# lightmeter_proto2.net
KiCad netlist of a schematic drawn in EAGLE
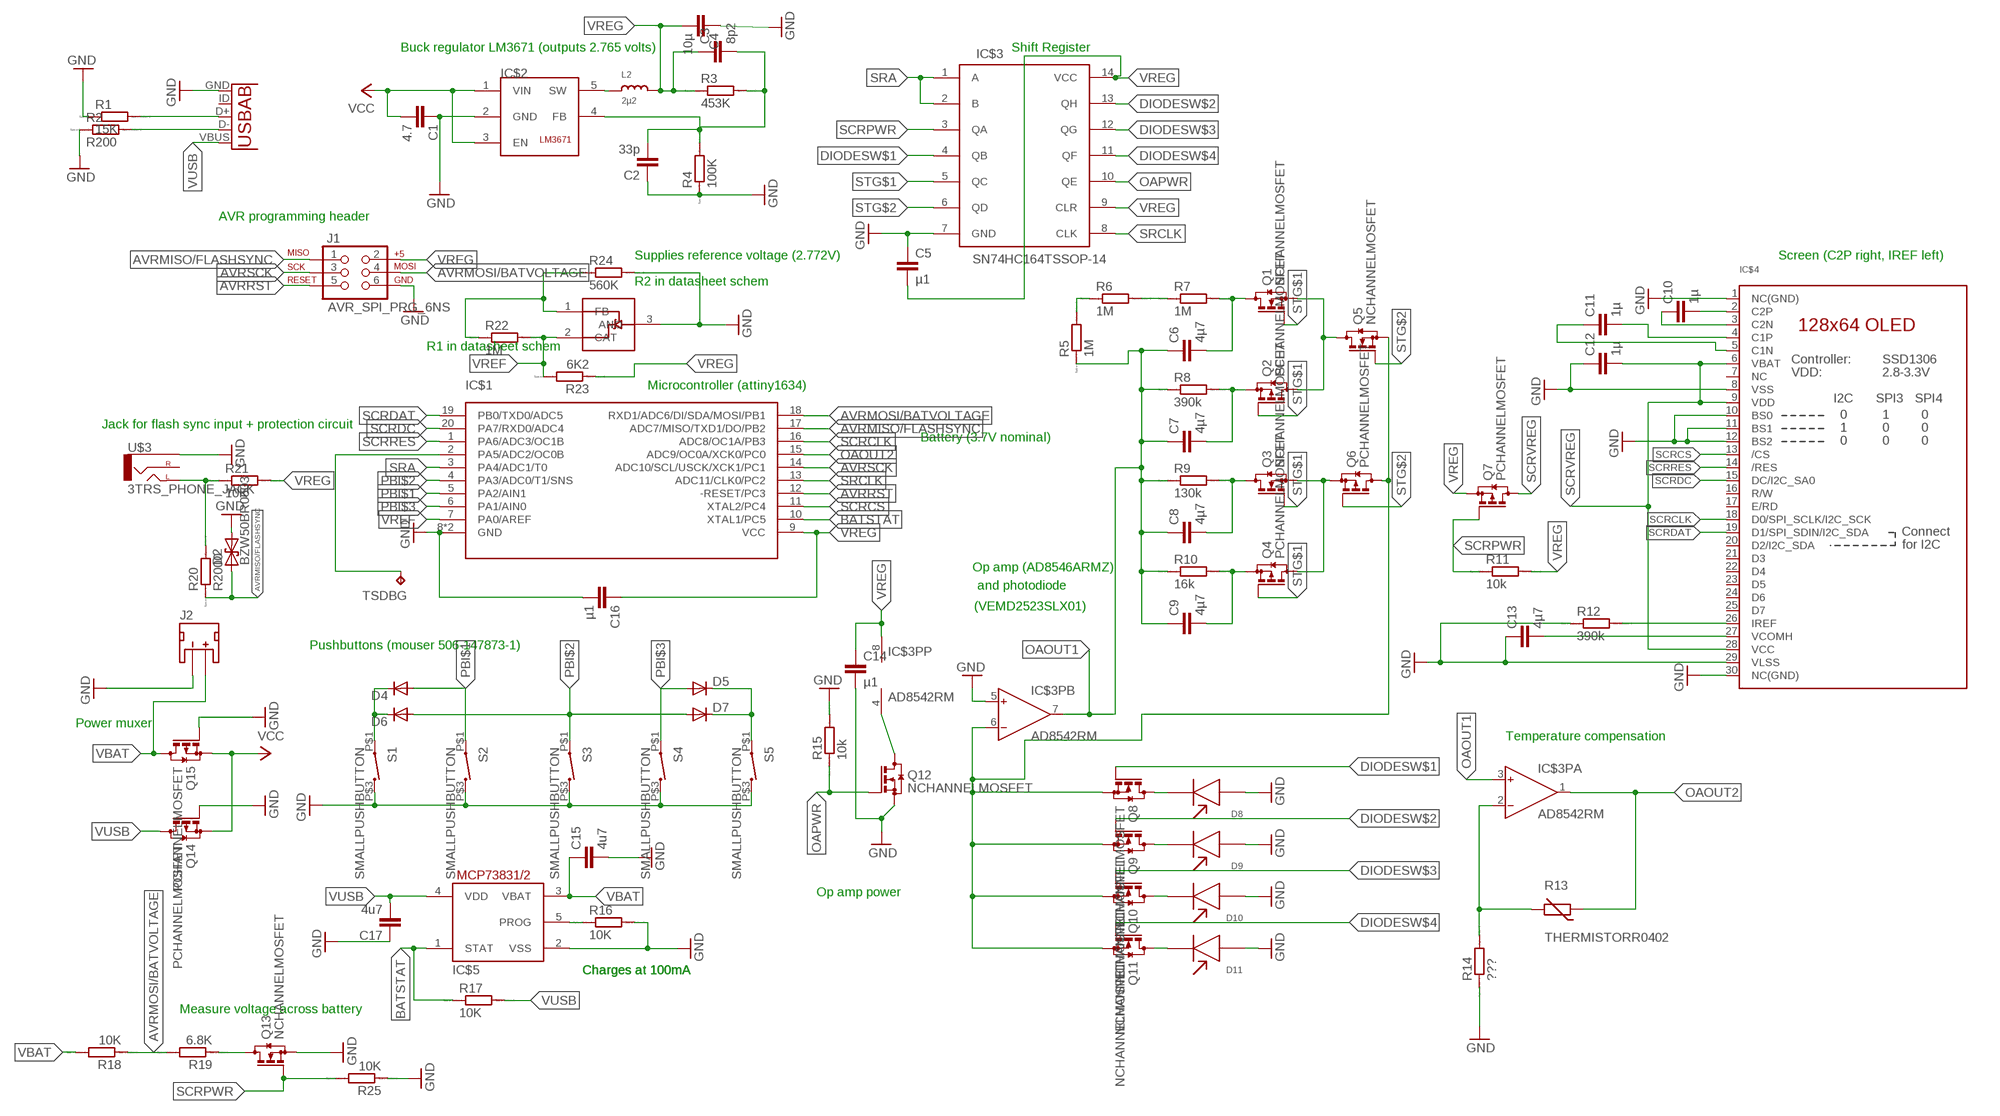
[diagram p0: schematic, sheet 1]

(export (version "E")
  (design (tool "Eeschema 10.0.6"))
  (components
    (comp (ref "C1")
      (value "4.7")
      (footprint "eagle-import:C0402")
      (libsource (lib "eagle-import") (part "C-EUC0402"))
    )
    (comp (ref "C2")
      (value "33p")
      (footprint "eagle-import:C0402")
      (libsource (lib "eagle-import") (part "C-EUC0402"))
    )
    (comp (ref "C3")
      (value "8p2")
      (footprint "eagle-import:C0402")
      (libsource (lib "eagle-import") (part "C-EUC0402"))
    )
    (comp (ref "C4")
      (value "10µ")
      (footprint "eagle-import:C0402")
      (libsource (lib "eagle-import") (part "C-EUC0402"))
    )
    (comp (ref "C5")
      (value "µ1")
      (footprint "eagle-import:C0402")
      (libsource (lib "eagle-import") (part "C-EUC0402"))
    )
    (comp (ref "C6")
      (value "4µ7")
      (footprint "eagle-import:C0402")
      (libsource (lib "eagle-import") (part "C-EUC0402"))
    )
    (comp (ref "C7")
      (value "4µ7")
      (footprint "eagle-import:C0402")
      (libsource (lib "eagle-import") (part "C-EUC0402"))
    )
    (comp (ref "C8")
      (value "4µ7")
      (footprint "eagle-import:C0402")
      (libsource (lib "eagle-import") (part "C-EUC0402"))
    )
    (comp (ref "C9")
      (value "4µ7")
      (footprint "eagle-import:C0402")
      (libsource (lib "eagle-import") (part "C-EUC0402"))
    )
    (comp (ref "C10")
      (value "1µ")
      (footprint "eagle-import:C0402")
      (libsource (lib "eagle-import") (part "C-EUC0402"))
    )
    (comp (ref "C11")
      (value "1µ")
      (footprint "eagle-import:C0402")
      (libsource (lib "eagle-import") (part "C-EUC0402"))
    )
    (comp (ref "C12")
      (value "1µ")
      (footprint "eagle-import:C0402")
      (libsource (lib "eagle-import") (part "C-EUC0402"))
    )
    (comp (ref "C13")
      (value "4µ7")
      (footprint "eagle-import:C0402")
      (libsource (lib "eagle-import") (part "C-EUC0402"))
    )
    (comp (ref "C14")
      (value "µ1")
      (footprint "eagle-import:C0402")
      (libsource (lib "eagle-import") (part "C-EUC0402"))
    )
    (comp (ref "C15")
      (value "4u7")
      (footprint "eagle-import:C0402")
      (libsource (lib "eagle-import") (part "C-EUC0402"))
    )
    (comp (ref "C16")
      (value "µ1")
      (footprint "eagle-import:C0402")
      (libsource (lib "eagle-import") (part "C-EUC0402"))
    )
    (comp (ref "C17")
      (value "4u7")
      (footprint "eagle-import:C0402")
      (libsource (lib "eagle-import") (part "C-EUC0402"))
    )
    (comp (ref "D2")
      (value "BZW50BR0603")
      (footprint "eagle-import:R0603")
      (libsource (lib "eagle-import") (part "BZW50BR0603"))
    )
    (comp (ref "D4")
      (value "DIODE-SOD323-W")
      (footprint "eagle-import:SOD323-W")
      (libsource (lib "eagle-import") (part "DIODE-SOD323-W"))
    )
    (comp (ref "D5")
      (value "DIODE-SOD323-W")
      (footprint "eagle-import:SOD323-W")
      (libsource (lib "eagle-import") (part "DIODE-SOD323-W"))
    )
    (comp (ref "D6")
      (value "DIODE-SOD323-W")
      (footprint "eagle-import:SOD323-W")
      (libsource (lib "eagle-import") (part "DIODE-SOD323-W"))
    )
    (comp (ref "D7")
      (value "DIODE-SOD323-W")
      (footprint "eagle-import:SOD323-W")
      (libsource (lib "eagle-import") (part "DIODE-SOD323-W"))
    )
    (comp (ref "D8")
      (value "VEMD2523SLX01")
      (footprint "eagle-import:VEMD2523SLX01")
      (libsource (lib "eagle-import") (part "VEMD2523SLX01"))
    )
    (comp (ref "D9")
      (value "VEMD2523SLX01")
      (footprint "eagle-import:VEMD2523SLX01")
      (libsource (lib "eagle-import") (part "VEMD2523SLX01"))
    )
    (comp (ref "D10")
      (value "VEMD2523SLX01")
      (footprint "eagle-import:VEMD2523SLX01")
      (libsource (lib "eagle-import") (part "VEMD2523SLX01"))
    )
    (comp (ref "D11")
      (value "VEMD2523SLX01")
      (footprint "eagle-import:VEMD2523SLX01")
      (libsource (lib "eagle-import") (part "VEMD2523SLX01"))
    )
    (comp (ref "IC$1")
      (value "ATTINY1634MLF20")
      (footprint "eagle-import:MLF20")
      (libsource (lib "eagle-import") (part "ATTINY1634MLF20"))
    )
    (comp (ref "IC$2")
      (value "LM3671")
      (footprint "eagle-import:SOT23-5")
      (libsource (lib "eagle-import") (part "LM3671"))
    )
    (comp (ref "IC$3")
      (value "SN74HC164TSSOP-14")
      (footprint "eagle-import:TSSOP14")
      (libsource (lib "eagle-import") (part "SN74HC164TSSOP-14"))
    )
    (comp (ref "IC$3P")
      (value "AD8542RM")
      (footprint "eagle-import:MSOP08")
      (fields (field (name "MPN") "AD8542ARZ"))
      (libsource (lib "eagle-import") (part "AD8542RM"))
    )
    (comp (ref "IC$4")
      (value "DISP_OLED_UG-2864HSWEG010.96\"")
      (footprint "eagle-import:UG-2864HSWEG01_0.96IN_WRAPAROUND")
      (libsource (lib "eagle-import") (part "DISP_OLED_UG-2864HSWEG010.96{dblquote}"))
    )
    (comp (ref "IC$5")
      (value "MCP73831/OT")
      (footprint "eagle-import:SOT23-5L")
      (libsource (lib "eagle-import") (part "MCP73831/OT"))
    )
    (comp (ref "IC$6")
      (value "TL4051")
      (footprint "eagle-import:SOT23")
      (libsource (lib "eagle-import") (part "TL4051"))
    )
    (comp (ref "J1")
      (value "AVR_SPI_PRG_6NS")
      (footprint "eagle-import:2X3-NS")
      (libsource (lib "eagle-import") (part "AVR_SPI_PRG_6NS"))
    )
    (comp (ref "J2")
      (value "JST_2MM_MALE")
      (footprint "eagle-import:JST-2-SMD")
      (libsource (lib "eagle-import") (part "JST_2MM_MALE"))
    )
    (comp (ref "L2")
      (value "2µ2")
      (footprint "eagle-import:_0402")
      (libsource (lib "eagle-import") (part "INDUCTOR_0402"))
    )
    (comp (ref "Q1")
      (value "NCHANNELMOSFET")
      (footprint "eagle-import:SOT-416-3")
      (libsource (lib "eagle-import") (part "NCHANNELMOSFET"))
    )
    (comp (ref "Q2")
      (value "PCHANNELMOSFET")
      (footprint "eagle-import:SOT-416-3")
      (libsource (lib "eagle-import") (part "PCHANNELMOSFET"))
    )
    (comp (ref "Q3")
      (value "NCHANNELMOSFET")
      (footprint "eagle-import:SOT-416-3")
      (libsource (lib "eagle-import") (part "NCHANNELMOSFET"))
    )
    (comp (ref "Q4")
      (value "PCHANNELMOSFET")
      (footprint "eagle-import:SOT-416-3")
      (libsource (lib "eagle-import") (part "PCHANNELMOSFET"))
    )
    (comp (ref "Q5")
      (value "NCHANNELMOSFET")
      (footprint "eagle-import:SOT-416-3")
      (libsource (lib "eagle-import") (part "NCHANNELMOSFET"))
    )
    (comp (ref "Q6")
      (value "PCHANNELMOSFET")
      (footprint "eagle-import:SOT-416-3")
      (libsource (lib "eagle-import") (part "PCHANNELMOSFET"))
    )
    (comp (ref "Q7")
      (value "PCHANNELMOSFET")
      (footprint "eagle-import:SOT-416-3")
      (libsource (lib "eagle-import") (part "PCHANNELMOSFET"))
    )
    (comp (ref "Q8")
      (value "NCHANNELMOSFET")
      (footprint "eagle-import:SOT-416-3")
      (libsource (lib "eagle-import") (part "NCHANNELMOSFET"))
    )
    (comp (ref "Q9")
      (value "NCHANNELMOSFET")
      (footprint "eagle-import:SOT-416-3")
      (libsource (lib "eagle-import") (part "NCHANNELMOSFET"))
    )
    (comp (ref "Q10")
      (value "NCHANNELMOSFET")
      (footprint "eagle-import:SOT-416-3")
      (libsource (lib "eagle-import") (part "NCHANNELMOSFET"))
    )
    (comp (ref "Q11")
      (value "NCHANNELMOSFET")
      (footprint "eagle-import:SOT-416-3")
      (libsource (lib "eagle-import") (part "NCHANNELMOSFET"))
    )
    (comp (ref "Q12")
      (value "NCHANNELMOSFET")
      (footprint "eagle-import:SOT-416-3")
      (libsource (lib "eagle-import") (part "NCHANNELMOSFET"))
    )
    (comp (ref "Q13")
      (value "NCHANNELMOSFET")
      (footprint "eagle-import:SOT-416-3")
      (libsource (lib "eagle-import") (part "NCHANNELMOSFET"))
    )
    (comp (ref "Q14")
      (value "PCHANNELMOSFET")
      (footprint "eagle-import:SOT-416-3")
      (libsource (lib "eagle-import") (part "PCHANNELMOSFET"))
    )
    (comp (ref "Q15")
      (value "PCHANNELMOSFET")
      (footprint "eagle-import:SOT-416-3")
      (libsource (lib "eagle-import") (part "PCHANNELMOSFET"))
    )
    (comp (ref "R1")
      (value "15K")
      (footprint "eagle-import:R0402")
      (libsource (lib "eagle-import") (part "R-EU_R0402"))
    )
    (comp (ref "R2")
      (value "R200")
      (footprint "eagle-import:R0402")
      (libsource (lib "eagle-import") (part "R-EU_R0402"))
    )
    (comp (ref "R3")
      (value "453K")
      (footprint "eagle-import:R0402")
      (libsource (lib "eagle-import") (part "R-EU_R0402"))
    )
    (comp (ref "R4")
      (value "100K")
      (footprint "eagle-import:R0402")
      (libsource (lib "eagle-import") (part "R-EU_R0402"))
    )
    (comp (ref "R5")
      (value "1M")
      (footprint "eagle-import:R0402")
      (libsource (lib "eagle-import") (part "R-EU_R0402"))
    )
    (comp (ref "R6")
      (value "1M")
      (footprint "eagle-import:R0402")
      (libsource (lib "eagle-import") (part "R-EU_R0402"))
    )
    (comp (ref "R7")
      (value "1M")
      (footprint "eagle-import:R0402")
      (libsource (lib "eagle-import") (part "R-EU_R0402"))
    )
    (comp (ref "R8")
      (value "390k")
      (footprint "eagle-import:R0402")
      (libsource (lib "eagle-import") (part "R-EU_R0402"))
    )
    (comp (ref "R9")
      (value "130k")
      (footprint "eagle-import:R0402")
      (libsource (lib "eagle-import") (part "R-EU_R0402"))
    )
    (comp (ref "R10")
      (value "16k")
      (footprint "eagle-import:R0402")
      (libsource (lib "eagle-import") (part "R-EU_R0402"))
    )
    (comp (ref "R11")
      (value "10k")
      (footprint "eagle-import:R0402")
      (libsource (lib "eagle-import") (part "R-EU_R0402"))
    )
    (comp (ref "R12")
      (value "390k")
      (footprint "eagle-import:R0402")
      (libsource (lib "eagle-import") (part "R-EU_R0402"))
    )
    (comp (ref "R13")
      (value "THERMISTORR0402")
      (footprint "eagle-import:R0402")
      (libsource (lib "eagle-import") (part "THERMISTORR0402"))
    )
    (comp (ref "R14")
      (value "???")
      (footprint "eagle-import:R0402")
      (libsource (lib "eagle-import") (part "R-EU_R0402"))
    )
    (comp (ref "R15")
      (value "10k")
      (footprint "eagle-import:R0402")
      (libsource (lib "eagle-import") (part "R-EU_R0402"))
    )
    (comp (ref "R16")
      (value "10K")
      (footprint "eagle-import:R0402")
      (libsource (lib "eagle-import") (part "R-EU_R0402"))
    )
    (comp (ref "R17")
      (value "10K")
      (footprint "eagle-import:R0402")
      (libsource (lib "eagle-import") (part "R-EU_R0402"))
    )
    (comp (ref "R18")
      (value "10K")
      (footprint "eagle-import:R0402")
      (libsource (lib "eagle-import") (part "R-EU_R0402"))
    )
    (comp (ref "R19")
      (value "6.8K")
      (footprint "eagle-import:R0402")
      (libsource (lib "eagle-import") (part "R-EU_R0402"))
    )
    (comp (ref "R20")
      (value "R2000")
      (footprint "eagle-import:R0402")
      (libsource (lib "eagle-import") (part "R-EU_R0402"))
    )
    (comp (ref "R21")
      (value "10K")
      (footprint "eagle-import:R0402")
      (libsource (lib "eagle-import") (part "R-EU_R0402"))
    )
    (comp (ref "R22")
      (value "1M")
      (footprint "eagle-import:R0402")
      (libsource (lib "eagle-import") (part "R-EU_R0402"))
    )
    (comp (ref "R23")
      (value "6K2")
      (footprint "eagle-import:R0402")
      (libsource (lib "eagle-import") (part "R-EU_R0402"))
    )
    (comp (ref "R24")
      (value "560K")
      (footprint "eagle-import:R0402")
      (libsource (lib "eagle-import") (part "R-EU_R0402"))
    )
    (comp (ref "R25")
      (value "10K")
      (footprint "eagle-import:R0402")
      (libsource (lib "eagle-import") (part "R-EU_R0402"))
    )
    (comp (ref "S1")
      (value "SMALLPUSHBUTTON")
      (footprint "eagle-import:BUTTON")
      (libsource (lib "eagle-import") (part "SMALLPUSHBUTTON"))
    )
    (comp (ref "S2")
      (value "SMALLPUSHBUTTON")
      (footprint "eagle-import:BUTTON")
      (libsource (lib "eagle-import") (part "SMALLPUSHBUTTON"))
    )
    (comp (ref "S3")
      (value "SMALLPUSHBUTTON")
      (footprint "eagle-import:BUTTON")
      (libsource (lib "eagle-import") (part "SMALLPUSHBUTTON"))
    )
    (comp (ref "S4")
      (value "SMALLPUSHBUTTON")
      (footprint "eagle-import:BUTTON")
      (libsource (lib "eagle-import") (part "SMALLPUSHBUTTON"))
    )
    (comp (ref "S5")
      (value "SMALLPUSHBUTTON")
      (footprint "eagle-import:BUTTON")
      (libsource (lib "eagle-import") (part "SMALLPUSHBUTTON"))
    )
    (comp (ref "TSDBG")
      (value "TPPAD1-13")
      (footprint "eagle-import:P1-13")
      (libsource (lib "eagle-import") (part "TPPAD1-13"))
    )
    (comp (ref "U$3")
      (value "3TRS_PHONE_JACK")
      (footprint "eagle-import:3TRS-SMD")
      (libsource (lib "eagle-import") (part "3TRS_PHONE_JACK"))
    )
    (comp (ref "U2")
      (value "USB-AB\"")
      (footprint "eagle-import:USB_AB_MICRO_1_1_V2")
      (libsource (lib "eagle-import") (part "USB-AB{dblquote}"))
    )
  )
  (nets
    (net (code "1") (name "AVRMISO{slash}FLASHSYNC") (class "Default")
      (node (ref "D2") (pin "1") (pinfunction "1_1") (pintype "passive"))
      (node (ref "IC$1") (pin "17") (pinfunction "ADC7/MISO/TXD1/DO/PB2_17") (pintype "bidirectional"))
      (node (ref "J1") (pin "1") (pinfunction "1_1") (pintype "passive"))
      (node (ref "R20") (pin "1") (pinfunction "1_1") (pintype "passive"))
    )
    (net (code "2") (name "AVRMOSI{slash}BATVOLTAGE") (class "Default")
      (node (ref "IC$1") (pin "18") (pinfunction "RXD1/ADC6/DI/SDA/MOSI/PB1_18") (pintype "bidirectional"))
      (node (ref "J1") (pin "4") (pinfunction "4_4") (pintype "passive"))
      (node (ref "R18") (pin "1") (pinfunction "1_1") (pintype "passive"))
      (node (ref "R19") (pin "2") (pinfunction "2_2") (pintype "passive"))
    )
    (net (code "3") (name "AVRRST") (class "Default")
      (node (ref "IC$1") (pin "12") (pinfunction "-RESET/PC3_12") (pintype "bidirectional"))
      (node (ref "J1") (pin "5") (pinfunction "5_5") (pintype "passive"))
    )
    (net (code "4") (name "AVRSCK") (class "Default")
      (node (ref "IC$1") (pin "14") (pinfunction "ADC10/SCL/USCK/XCK1/PC1_14") (pintype "bidirectional"))
      (node (ref "J1") (pin "3") (pinfunction "3_3") (pintype "passive"))
    )
    (net (code "5") (name "BATSTAT") (class "Default")
      (node (ref "IC$1") (pin "10") (pinfunction "XTAL1/PC5_10") (pintype "bidirectional"))
      (node (ref "IC$5") (pin "1") (pinfunction "STAT_1") (pintype "output"))
      (node (ref "R17") (pin "1") (pinfunction "1_1") (pintype "passive"))
    )
    (net (code "6") (name "DIODESW$1") (class "Default")
      (node (ref "IC$3") (pin "4") (pinfunction "QB_4") (pintype "bidirectional"))
      (node (ref "Q8") (pin "P$1") (pinfunction "G_P$1") (pintype "passive"))
    )
    (net (code "7") (name "DIODESW$2") (class "Default")
      (node (ref "IC$3") (pin "13") (pinfunction "QH_13") (pintype "bidirectional"))
      (node (ref "Q9") (pin "P$1") (pinfunction "G_P$1") (pintype "passive"))
    )
    (net (code "8") (name "DIODESW$3") (class "Default")
      (node (ref "IC$3") (pin "12") (pinfunction "QG_12") (pintype "bidirectional"))
      (node (ref "Q10") (pin "P$1") (pinfunction "G_P$1") (pintype "passive"))
    )
    (net (code "9") (name "DIODESW$4") (class "Default")
      (node (ref "IC$3") (pin "11") (pinfunction "QF_11") (pintype "bidirectional"))
      (node (ref "Q11") (pin "P$1") (pinfunction "G_P$1") (pintype "passive"))
    )
    (net (code "10") (name "GND") (class "Default")
      (node (ref "C1") (pin "1") (pinfunction "1_1") (pintype "passive"))
      (node (ref "C12") (pin "1") (pinfunction "1_1") (pintype "passive"))
      (node (ref "C13") (pin "1") (pinfunction "1_1") (pintype "passive"))
      (node (ref "C14") (pin "2") (pinfunction "2_2") (pintype "passive"))
      (node (ref "C15") (pin "2") (pinfunction "2_2") (pintype "passive"))
      (node (ref "C16") (pin "2") (pinfunction "2_2") (pintype "passive"))
      (node (ref "C17") (pin "1") (pinfunction "1_1") (pintype "passive"))
      (node (ref "C2") (pin "1") (pinfunction "1_1") (pintype "passive"))
      (node (ref "C4") (pin "1") (pinfunction "1_1") (pintype "passive"))
      (node (ref "C5") (pin "1") (pinfunction "1_1") (pintype "passive"))
      (node (ref "D10") (pin "P$1") (pinfunction "P$1_P$1") (pintype "bidirectional"))
      (node (ref "D11") (pin "P$1") (pinfunction "P$1_P$1") (pintype "bidirectional"))
      (node (ref "D2") (pin "2") (pinfunction "2_2") (pintype "passive"))
      (node (ref "D8") (pin "P$1") (pinfunction "P$1_P$1") (pintype "bidirectional"))
      (node (ref "D9") (pin "P$1") (pinfunction "P$1_P$1") (pintype "bidirectional"))
      (node (ref "IC$1") (pin "8") (pinfunction "GND_8") (pintype "power_in"))
      (node (ref "IC$1") (pin "GND") (pinfunction "GND_GND") (pintype "power_in"))
      (node (ref "IC$2") (pin "2") (pinfunction "GND_2") (pintype "bidirectional"))
      (node (ref "IC$3") (pin "7") (pinfunction "GND_7") (pintype "bidirectional"))
      (node (ref "IC$3P") (pin "5") (pinfunction "IN+_5") (pintype "input"))
      (node (ref "IC$4") (pin "1") (pinfunction "NC(GND)_1") (pintype "input"))
      (node (ref "IC$4") (pin "10") (pinfunction "BS0_10") (pintype "input"))
      (node (ref "IC$4") (pin "11") (pinfunction "BS1_11") (pintype "input"))
      (node (ref "IC$4") (pin "12") (pinfunction "BS2_12") (pintype "input"))
      (node (ref "IC$4") (pin "29") (pinfunction "VLSS_29") (pintype "power_in"))
      (node (ref "IC$4") (pin "30") (pinfunction "NC(GND)_30") (pintype "input"))
      (node (ref "IC$4") (pin "8") (pinfunction "VSS_8") (pintype "power_in"))
      (node (ref "IC$5") (pin "2") (pinfunction "VSS_2") (pintype "power_in"))
      (node (ref "IC$6") (pin "3") (pinfunction "ANO_3") (pintype "bidirectional"))
      (node (ref "J1") (pin "6") (pinfunction "6_6") (pintype "passive"))
      (node (ref "J2") (pin "1") (pinfunction "-_1") (pintype "bidirectional"))
      (node (ref "Q12") (pin "P$2") (pinfunction "S_P$2") (pintype "passive"))
      (node (ref "Q13") (pin "P$2") (pinfunction "S_P$2") (pintype "passive"))
      (node (ref "Q14") (pin "P$1") (pinfunction "G_P$1") (pintype "passive"))
      (node (ref "Q15") (pin "P$1") (pinfunction "G_P$1") (pintype "passive"))
      (node (ref "R1") (pin "1") (pinfunction "1_1") (pintype "passive"))
      (node (ref "R12") (pin "1") (pinfunction "1_1") (pintype "passive"))
      (node (ref "R14") (pin "1") (pinfunction "1_1") (pintype "passive"))
      (node (ref "R15") (pin "2") (pinfunction "2_2") (pintype "passive"))
      (node (ref "R16") (pin "2") (pinfunction "2_2") (pintype "passive"))
      (node (ref "R2") (pin "1") (pinfunction "1_1") (pintype "passive"))
      (node (ref "R24") (pin "2") (pinfunction "2_2") (pintype "passive"))
      (node (ref "R25") (pin "1") (pinfunction "1_1") (pintype "passive"))
      (node (ref "R4") (pin "1") (pinfunction "1_1") (pintype "passive"))
      (node (ref "S1") (pin "P$3") (pinfunction "2_P$3") (pintype "passive"))
      (node (ref "S2") (pin "P$3") (pinfunction "2_P$3") (pintype "passive"))
      (node (ref "S3") (pin "P$3") (pinfunction "2_P$3") (pintype "passive"))
      (node (ref "S4") (pin "P$3") (pinfunction "2_P$3") (pintype "passive"))
      (node (ref "S5") (pin "P$3") (pinfunction "2_P$3") (pintype "passive"))
      (node (ref "U$3") (pin "P$1") (pinfunction "SLEEVE_P$1") (pintype "bidirectional"))
      (node (ref "U2") (pin "GND") (pinfunction "GND_GND") (pintype "bidirectional"))
    )
    (net (code "11") (name "Net-(IC$1-PA5{slash}ADC2{slash}OC0B)") (class "Default")
      (node (ref "IC$1") (pin "2") (pinfunction "PA5/ADC2/OC0B_2") (pintype "bidirectional"))
      (node (ref "TSDBG") (pin "TP") (pinfunction "TP_TP") (pintype "input"))
    )
    (net (code "12") (name "Net-(IC$2-FB)") (class "Default")
      (node (ref "C2") (pin "2") (pinfunction "2_2") (pintype "passive"))
      (node (ref "C3") (pin "2") (pinfunction "2_2") (pintype "passive"))
      (node (ref "IC$2") (pin "4") (pinfunction "FB_4") (pintype "bidirectional"))
      (node (ref "R3") (pin "2") (pinfunction "2_2") (pintype "passive"))
      (node (ref "R4") (pin "2") (pinfunction "2_2") (pintype "passive"))
    )
    (net (code "13") (name "Net-(IC$2-SW)") (class "Default")
      (node (ref "IC$2") (pin "5") (pinfunction "SW_5") (pintype "bidirectional"))
      (node (ref "L2") (pin "1") (pinfunction "1_1") (pintype "passive"))
    )
    (net (code "14") (name "Net-(IC$3PA-IN-)") (class "Default")
      (node (ref "IC$3P") (pin "2") (pinfunction "IN-_2") (pintype "input"))
      (node (ref "R13") (pin "2") (pinfunction "2_2") (pintype "passive"))
      (node (ref "R14") (pin "2") (pinfunction "2_2") (pintype "passive"))
    )
    (net (code "15") (name "Net-(IC$3PB-IN-)") (class "Default")
      (node (ref "IC$3P") (pin "6") (pinfunction "IN-_6") (pintype "input"))
      (node (ref "Q10") (pin "P$2") (pinfunction "S_P$2") (pintype "passive"))
      (node (ref "Q11") (pin "P$2") (pinfunction "S_P$2") (pintype "passive"))
      (node (ref "Q5") (pin "P$2") (pinfunction "S_P$2") (pintype "passive"))
      (node (ref "Q6") (pin "P$3") (pinfunction "D_P$3") (pintype "passive"))
      (node (ref "Q8") (pin "P$2") (pinfunction "S_P$2") (pintype "passive"))
      (node (ref "Q9") (pin "P$2") (pinfunction "S_P$2") (pintype "passive"))
    )
    (net (code "16") (name "Net-(IC$3PC-V-)") (class "Default")
      (node (ref "IC$3P") (pin "4") (pinfunction "V-_4") (pintype "power_in"))
      (node (ref "Q12") (pin "P$3") (pinfunction "D_P$3") (pintype "passive"))
    )
    (net (code "17") (name "Net-(IC$4-C1N)") (class "Default")
      (node (ref "C11") (pin "1") (pinfunction "1_1") (pintype "passive"))
      (node (ref "IC$4") (pin "5") (pinfunction "C1N_5") (pintype "input"))
    )
    (net (code "18") (name "Net-(IC$4-C1P)") (class "Default")
      (node (ref "C11") (pin "2") (pinfunction "2_2") (pintype "passive"))
      (node (ref "IC$4") (pin "4") (pinfunction "C1P_4") (pintype "input"))
    )
    (net (code "19") (name "Net-(IC$4-C2N)") (class "Default")
      (node (ref "C10") (pin "1") (pinfunction "1_1") (pintype "passive"))
      (node (ref "IC$4") (pin "3") (pinfunction "C2N_3") (pintype "input"))
    )
    (net (code "20") (name "Net-(IC$4-C2P)") (class "Default")
      (node (ref "C10") (pin "2") (pinfunction "2_2") (pintype "passive"))
      (node (ref "IC$4") (pin "2") (pinfunction "C2P_2") (pintype "input"))
    )
    (net (code "21") (name "Net-(IC$4-IREF)") (class "Default")
      (node (ref "IC$4") (pin "26") (pinfunction "IREF_26") (pintype "input"))
      (node (ref "R12") (pin "2") (pinfunction "2_2") (pintype "passive"))
    )
    (net (code "22") (name "Net-(IC$4-VCOMH)") (class "Default")
      (node (ref "C13") (pin "2") (pinfunction "2_2") (pintype "passive"))
      (node (ref "IC$4") (pin "27") (pinfunction "VCOMH_27") (pintype "output"))
    )
    (net (code "23") (name "Net-(IC$5-PROG)") (class "Default")
      (node (ref "IC$5") (pin "5") (pinfunction "PROG_5") (pintype "input"))
      (node (ref "R16") (pin "1") (pinfunction "1_1") (pintype "passive"))
    )
    (net (code "24") (name "Net-(IC$6-FB)") (class "Default")
      (node (ref "IC$6") (pin "1") (pinfunction "FB_1") (pintype "bidirectional"))
      (node (ref "R22") (pin "1") (pinfunction "1_1") (pintype "passive"))
      (node (ref "R24") (pin "1") (pinfunction "1_1") (pintype "passive"))
    )
    (net (code "25") (name "Net-(Q1-D)") (class "Default")
      (node (ref "C6") (pin "2") (pinfunction "2_2") (pintype "passive"))
      (node (ref "Q1") (pin "P$3") (pinfunction "D_P$3") (pintype "passive"))
      (node (ref "R7") (pin "2") (pinfunction "2_2") (pintype "passive"))
    )
    (net (code "26") (name "Net-(Q1-S)") (class "Default")
      (node (ref "Q1") (pin "P$2") (pinfunction "S_P$2") (pintype "passive"))
      (node (ref "Q2") (pin "P$3") (pinfunction "D_P$3") (pintype "passive"))
      (node (ref "Q5") (pin "P$3") (pinfunction "D_P$3") (pintype "passive"))
    )
    (net (code "27") (name "Net-(Q2-S)") (class "Default")
      (node (ref "C7") (pin "2") (pinfunction "2_2") (pintype "passive"))
      (node (ref "Q2") (pin "P$2") (pinfunction "S_P$2") (pintype "passive"))
      (node (ref "R8") (pin "2") (pinfunction "2_2") (pintype "passive"))
    )
    (net (code "28") (name "Net-(Q3-D)") (class "Default")
      (node (ref "C8") (pin "2") (pinfunction "2_2") (pintype "passive"))
      (node (ref "Q3") (pin "P$3") (pinfunction "D_P$3") (pintype "passive"))
      (node (ref "R9") (pin "2") (pinfunction "2_2") (pintype "passive"))
    )
    (net (code "29") (name "Net-(Q3-S)") (class "Default")
      (node (ref "Q3") (pin "P$2") (pinfunction "S_P$2") (pintype "passive"))
      (node (ref "Q4") (pin "P$3") (pinfunction "D_P$3") (pintype "passive"))
      (node (ref "Q6") (pin "P$2") (pinfunction "S_P$2") (pintype "passive"))
    )
    (net (code "30") (name "Net-(Q4-S)") (class "Default")
      (node (ref "C9") (pin "2") (pinfunction "2_2") (pintype "passive"))
      (node (ref "Q4") (pin "P$2") (pinfunction "S_P$2") (pintype "passive"))
      (node (ref "R10") (pin "2") (pinfunction "2_2") (pintype "passive"))
    )
    (net (code "31") (name "Net-(Q8-D)") (class "Default")
      (node (ref "D8") (pin "P$2") (pinfunction "P$2_P$2") (pintype "bidirectional"))
      (node (ref "Q8") (pin "P$3") (pinfunction "D_P$3") (pintype "passive"))
    )
    (net (code "32") (name "Net-(Q9-D)") (class "Default")
      (node (ref "D9") (pin "P$2") (pinfunction "P$2_P$2") (pintype "bidirectional"))
      (node (ref "Q9") (pin "P$3") (pinfunction "D_P$3") (pintype "passive"))
    )
    (net (code "33") (name "Net-(Q10-D)") (class "Default")
      (node (ref "D10") (pin "P$2") (pinfunction "P$2_P$2") (pintype "bidirectional"))
      (node (ref "Q10") (pin "P$3") (pinfunction "D_P$3") (pintype "passive"))
    )
    (net (code "34") (name "Net-(Q11-D)") (class "Default")
      (node (ref "D11") (pin "P$2") (pinfunction "P$2_P$2") (pintype "bidirectional"))
      (node (ref "Q11") (pin "P$3") (pinfunction "D_P$3") (pintype "passive"))
    )
    (net (code "35") (name "Net-(Q13-D)") (class "Default")
      (node (ref "Q13") (pin "P$3") (pinfunction "D_P$3") (pintype "passive"))
      (node (ref "R19") (pin "1") (pinfunction "1_1") (pintype "passive"))
    )
    (net (code "36") (name "Net-(R1-Pad2)") (class "Default")
      (node (ref "R1") (pin "2") (pinfunction "2_2") (pintype "passive"))
      (node (ref "U2") (pin "D+") (pinfunction "D+_D+") (pintype "bidirectional"))
    )
    (net (code "37") (name "Net-(R2-Pad2)") (class "Default")
      (node (ref "R2") (pin "2") (pinfunction "2_2") (pintype "passive"))
      (node (ref "U2") (pin "D-") (pinfunction "D-_D-") (pintype "bidirectional"))
    )
    (net (code "38") (name "Net-(R5-Pad2)") (class "Default")
      (node (ref "R5") (pin "2") (pinfunction "2_2") (pintype "passive"))
      (node (ref "R6") (pin "1") (pinfunction "1_1") (pintype "passive"))
    )
    (net (code "39") (name "Net-(R6-Pad2)") (class "Default")
      (node (ref "R6") (pin "2") (pinfunction "2_2") (pintype "passive"))
      (node (ref "R7") (pin "1") (pinfunction "1_1") (pintype "passive"))
    )
    (net (code "40") (name "Net-(S1-1)") (class "Default")
      (node (ref "D4") (pin "C") (pinfunction "C_C") (pintype "passive"))
      (node (ref "D6") (pin "C") (pinfunction "C_C") (pintype "passive"))
      (node (ref "S1") (pin "P$1") (pinfunction "1_P$1") (pintype "passive"))
    )
    (net (code "41") (name "Net-(S5-1)") (class "Default")
      (node (ref "D5") (pin "C") (pinfunction "C_C") (pintype "passive"))
      (node (ref "D7") (pin "C") (pinfunction "C_C") (pintype "passive"))
      (node (ref "S5") (pin "P$1") (pinfunction "1_P$1") (pintype "passive"))
    )
    (net (code "42") (name "Net-(U$3-LEFT)") (class "Default")
      (node (ref "R20") (pin "2") (pinfunction "2_2") (pintype "passive"))
      (node (ref "R21") (pin "1") (pinfunction "1_1") (pintype "passive"))
      (node (ref "U$3") (pin "P$3") (pinfunction "LEFT_P$3") (pintype "bidirectional"))
    )
    (net (code "43") (name "OAOUT1") (class "Default")
      (node (ref "C6") (pin "1") (pinfunction "1_1") (pintype "passive"))
      (node (ref "C7") (pin "1") (pinfunction "1_1") (pintype "passive"))
      (node (ref "C8") (pin "1") (pinfunction "1_1") (pintype "passive"))
      (node (ref "C9") (pin "1") (pinfunction "1_1") (pintype "passive"))
      (node (ref "IC$3P") (pin "3") (pinfunction "IN+_3") (pintype "input"))
      (node (ref "IC$3P") (pin "7") (pinfunction "OUT_7") (pintype "output"))
      (node (ref "R10") (pin "1") (pinfunction "1_1") (pintype "passive"))
      (node (ref "R5") (pin "1") (pinfunction "1_1") (pintype "passive"))
      (node (ref "R8") (pin "1") (pinfunction "1_1") (pintype "passive"))
      (node (ref "R9") (pin "1") (pinfunction "1_1") (pintype "passive"))
    )
    (net (code "44") (name "OAOUT2") (class "Default")
      (node (ref "IC$1") (pin "15") (pinfunction "ADC9/OC0A/XCK0/PC0_15") (pintype "bidirectional"))
      (node (ref "IC$3P") (pin "1") (pinfunction "OUT_1") (pintype "output"))
      (node (ref "R13") (pin "1") (pinfunction "1_1") (pintype "passive"))
    )
    (net (code "45") (name "OAPWR") (class "Default")
      (node (ref "IC$3") (pin "10") (pinfunction "QE_10") (pintype "bidirectional"))
      (node (ref "Q12") (pin "P$1") (pinfunction "G_P$1") (pintype "passive"))
      (node (ref "R15") (pin "1") (pinfunction "1_1") (pintype "passive"))
    )
    (net (code "46") (name "PBI$1") (class "Default")
      (node (ref "D4") (pin "A") (pinfunction "A_A") (pintype "passive"))
      (node (ref "IC$1") (pin "5") (pinfunction "PA2/AIN1_5") (pintype "bidirectional"))
      (node (ref "S2") (pin "P$1") (pinfunction "1_P$1") (pintype "passive"))
    )
    (net (code "47") (name "PBI$2") (class "Default")
      (node (ref "D6") (pin "A") (pinfunction "A_A") (pintype "passive"))
      (node (ref "D7") (pin "A") (pinfunction "A_A") (pintype "passive"))
      (node (ref "IC$1") (pin "4") (pinfunction "PA3/ADC0/T1/SNS_4") (pintype "bidirectional"))
      (node (ref "S3") (pin "P$1") (pinfunction "1_P$1") (pintype "passive"))
    )
    (net (code "48") (name "PBI$3") (class "Default")
      (node (ref "D5") (pin "A") (pinfunction "A_A") (pintype "passive"))
      (node (ref "IC$1") (pin "6") (pinfunction "PA1/AIN0_6") (pintype "bidirectional"))
      (node (ref "S4") (pin "P$1") (pinfunction "1_P$1") (pintype "passive"))
    )
    (net (code "49") (name "SCRCLK") (class "Default")
      (node (ref "IC$1") (pin "16") (pinfunction "ADC8/OC1A/PB3_16") (pintype "bidirectional"))
      (node (ref "IC$4") (pin "18") (pinfunction "D0/SPI_SCLK/I2C_SCK_18") (pintype "bidirectional"))
    )
    (net (code "50") (name "SCRCS") (class "Default")
      (node (ref "IC$1") (pin "11") (pinfunction "XTAL2/PC4_11") (pintype "bidirectional"))
      (node (ref "IC$4") (pin "13") (pinfunction "/CS_13") (pintype "input"))
    )
    (net (code "51") (name "SCRDAT") (class "Default")
      (node (ref "IC$1") (pin "19") (pinfunction "PB0/TXD0/ADC5_19") (pintype "bidirectional"))
      (node (ref "IC$4") (pin "19") (pinfunction "D1/SPI_SDIN/I2C_SDA_19") (pintype "bidirectional"))
    )
    (net (code "52") (name "SCRDC") (class "Default")
      (node (ref "IC$1") (pin "20") (pinfunction "PA7/RXD0/ADC4_20") (pintype "bidirectional"))
      (node (ref "IC$4") (pin "15") (pinfunction "DC/I2C_SA0_15") (pintype "input"))
    )
    (net (code "53") (name "SCRPWR") (class "Default")
      (node (ref "IC$3") (pin "3") (pinfunction "QA_3") (pintype "bidirectional"))
      (node (ref "Q13") (pin "P$1") (pinfunction "G_P$1") (pintype "passive"))
      (node (ref "Q7") (pin "P$1") (pinfunction "G_P$1") (pintype "passive"))
      (node (ref "R11") (pin "1") (pinfunction "1_1") (pintype "passive"))
      (node (ref "R25") (pin "2") (pinfunction "2_2") (pintype "passive"))
    )
    (net (code "54") (name "SCRRES") (class "Default")
      (node (ref "IC$1") (pin "1") (pinfunction "PA6/ADC3/OC1B_1") (pintype "bidirectional"))
      (node (ref "IC$4") (pin "14") (pinfunction "/RES_14") (pintype "input"))
    )
    (net (code "55") (name "SCRVREG") (class "Default")
      (node (ref "C12") (pin "2") (pinfunction "2_2") (pintype "passive"))
      (node (ref "IC$4") (pin "28") (pinfunction "VCC_28") (pintype "power_in"))
      (node (ref "IC$4") (pin "6") (pinfunction "VBAT_6") (pintype "input"))
      (node (ref "IC$4") (pin "9") (pinfunction "VDD_9") (pintype "power_in"))
      (node (ref "Q7") (pin "P$3") (pinfunction "D_P$3") (pintype "passive"))
    )
    (net (code "56") (name "SRA") (class "Default")
      (node (ref "IC$1") (pin "3") (pinfunction "PA4/ADC1/T0_3") (pintype "bidirectional"))
      (node (ref "IC$3") (pin "1") (pinfunction "A_1") (pintype "bidirectional"))
      (node (ref "IC$3") (pin "2") (pinfunction "B_2") (pintype "bidirectional"))
    )
    (net (code "57") (name "SRCLK") (class "Default")
      (node (ref "IC$1") (pin "13") (pinfunction "ADC11/CLK0/PC2_13") (pintype "bidirectional"))
      (node (ref "IC$3") (pin "8") (pinfunction "CLK_8") (pintype "bidirectional"))
    )
    (net (code "58") (name "STG$1") (class "Default")
      (node (ref "IC$3") (pin "5") (pinfunction "QC_5") (pintype "bidirectional"))
      (node (ref "Q1") (pin "P$1") (pinfunction "G_P$1") (pintype "passive"))
      (node (ref "Q2") (pin "P$1") (pinfunction "G_P$1") (pintype "passive"))
      (node (ref "Q3") (pin "P$1") (pinfunction "G_P$1") (pintype "passive"))
      (node (ref "Q4") (pin "P$1") (pinfunction "G_P$1") (pintype "passive"))
    )
    (net (code "59") (name "STG$2") (class "Default")
      (node (ref "IC$3") (pin "6") (pinfunction "QD_6") (pintype "bidirectional"))
      (node (ref "Q5") (pin "P$1") (pinfunction "G_P$1") (pintype "passive"))
      (node (ref "Q6") (pin "P$1") (pinfunction "G_P$1") (pintype "passive"))
    )
    (net (code "60") (name "VBAT") (class "Default")
      (node (ref "C15") (pin "1") (pinfunction "1_1") (pintype "passive"))
      (node (ref "IC$5") (pin "3") (pinfunction "VBAT_3") (pintype "bidirectional"))
      (node (ref "J2") (pin "2") (pinfunction "+_2") (pintype "bidirectional"))
      (node (ref "Q15") (pin "P$3") (pinfunction "D_P$3") (pintype "passive"))
      (node (ref "R18") (pin "2") (pinfunction "2_2") (pintype "passive"))
    )
    (net (code "61") (name "VCC") (class "Default")
      (node (ref "C1") (pin "2") (pinfunction "2_2") (pintype "passive"))
      (node (ref "IC$2") (pin "1") (pinfunction "VIN_1") (pintype "bidirectional"))
      (node (ref "IC$2") (pin "3") (pinfunction "EN_3") (pintype "bidirectional"))
      (node (ref "Q14") (pin "P$2") (pinfunction "S_P$2") (pintype "passive"))
      (node (ref "Q15") (pin "P$2") (pinfunction "S_P$2") (pintype "passive"))
    )
    (net (code "62") (name "VREF") (class "Default")
      (node (ref "IC$1") (pin "7") (pinfunction "PA0/AREF_7") (pintype "bidirectional"))
      (node (ref "IC$6") (pin "2") (pinfunction "CAT_2") (pintype "bidirectional"))
      (node (ref "R22") (pin "2") (pinfunction "2_2") (pintype "passive"))
      (node (ref "R23") (pin "2") (pinfunction "2_2") (pintype "passive"))
    )
    (net (code "63") (name "VREG") (class "Default")
      (node (ref "C14") (pin "1") (pinfunction "1_1") (pintype "passive"))
      (node (ref "C16") (pin "1") (pinfunction "1_1") (pintype "passive"))
      (node (ref "C3") (pin "1") (pinfunction "1_1") (pintype "passive"))
      (node (ref "C4") (pin "2") (pinfunction "2_2") (pintype "passive"))
      (node (ref "C5") (pin "2") (pinfunction "2_2") (pintype "passive"))
      (node (ref "IC$1") (pin "9") (pinfunction "VCC_9") (pintype "power_in"))
      (node (ref "IC$3") (pin "14") (pinfunction "VCC_14") (pintype "bidirectional"))
      (node (ref "IC$3") (pin "9") (pinfunction "CLR_9") (pintype "bidirectional"))
      (node (ref "IC$3P") (pin "8") (pinfunction "V+_8") (pintype "power_in"))
      (node (ref "J1") (pin "2") (pinfunction "2_2") (pintype "passive"))
      (node (ref "L2") (pin "2") (pinfunction "2_2") (pintype "passive"))
      (node (ref "Q7") (pin "P$2") (pinfunction "S_P$2") (pintype "passive"))
      (node (ref "R11") (pin "2") (pinfunction "2_2") (pintype "passive"))
      (node (ref "R21") (pin "2") (pinfunction "2_2") (pintype "passive"))
      (node (ref "R23") (pin "1") (pinfunction "1_1") (pintype "passive"))
      (node (ref "R3") (pin "1") (pinfunction "1_1") (pintype "passive"))
    )
    (net (code "64") (name "VUSB") (class "Default")
      (node (ref "C17") (pin "2") (pinfunction "2_2") (pintype "passive"))
      (node (ref "IC$5") (pin "4") (pinfunction "VDD_4") (pintype "power_in"))
      (node (ref "Q14") (pin "P$3") (pinfunction "D_P$3") (pintype "passive"))
      (node (ref "R17") (pin "2") (pinfunction "2_2") (pintype "passive"))
      (node (ref "U2") (pin "VBUS") (pinfunction "VBUS_VBUS") (pintype "bidirectional"))
    )
    (net (code "65") (name "unconnected-(IC$4-D2{slash}I2C_SDA-Pad20)") (class "Default")
      (node (ref "IC$4") (pin "20") (pinfunction "D2/I2C_SDA_20") (pintype "bidirectional"))
    )
    (net (code "66") (name "unconnected-(IC$4-D3-Pad21)") (class "Default")
      (node (ref "IC$4") (pin "21") (pinfunction "D3_21") (pintype "bidirectional"))
    )
    (net (code "67") (name "unconnected-(IC$4-D4-Pad22)") (class "Default")
      (node (ref "IC$4") (pin "22") (pinfunction "D4_22") (pintype "bidirectional"))
    )
    (net (code "68") (name "unconnected-(IC$4-D5-Pad23)") (class "Default")
      (node (ref "IC$4") (pin "23") (pinfunction "D5_23") (pintype "bidirectional"))
    )
    (net (code "69") (name "unconnected-(IC$4-D6-Pad24)") (class "Default")
      (node (ref "IC$4") (pin "24") (pinfunction "D6_24") (pintype "bidirectional"))
    )
    (net (code "70") (name "unconnected-(IC$4-D7-Pad25)") (class "Default")
      (node (ref "IC$4") (pin "25") (pinfunction "D7_25") (pintype "bidirectional"))
    )
    (net (code "71") (name "unconnected-(IC$4-E{slash}RD-Pad17)") (class "Default")
      (node (ref "IC$4") (pin "17") (pinfunction "E/RD_17") (pintype "input"))
    )
    (net (code "72") (name "unconnected-(IC$4-NC-Pad7)") (class "Default")
      (node (ref "IC$4") (pin "7") (pinfunction "NC_7") (pintype "no_connect"))
    )
    (net (code "73") (name "unconnected-(IC$4-R{slash}W-Pad16)") (class "Default")
      (node (ref "IC$4") (pin "16") (pinfunction "R/W_16") (pintype "input"))
    )
    (net (code "74") (name "unconnected-(J2-PAD1-PadNC1)") (class "Default")
      (node (ref "J2") (pin "NC1") (pinfunction "PAD1_NC1") (pintype "bidirectional"))
    )
    (net (code "75") (name "unconnected-(J2-PAD2-PadNC2)") (class "Default")
      (node (ref "J2") (pin "NC2") (pinfunction "PAD2_NC2") (pintype "bidirectional"))
    )
    (net (code "76") (name "unconnected-(U$3-RIGHT-PadP$2)") (class "Default")
      (node (ref "U$3") (pin "P$2") (pinfunction "RIGHT_P$2") (pintype "bidirectional"))
    )
    (net (code "77") (name "unconnected-(U2-USBID-PadID)") (class "Default")
      (node (ref "U2") (pin "ID") (pinfunction "USBID_ID") (pintype "bidirectional"))
    )
  )
)
